# interface.net
KiCad netlist of a schematic drawn in EAGLE
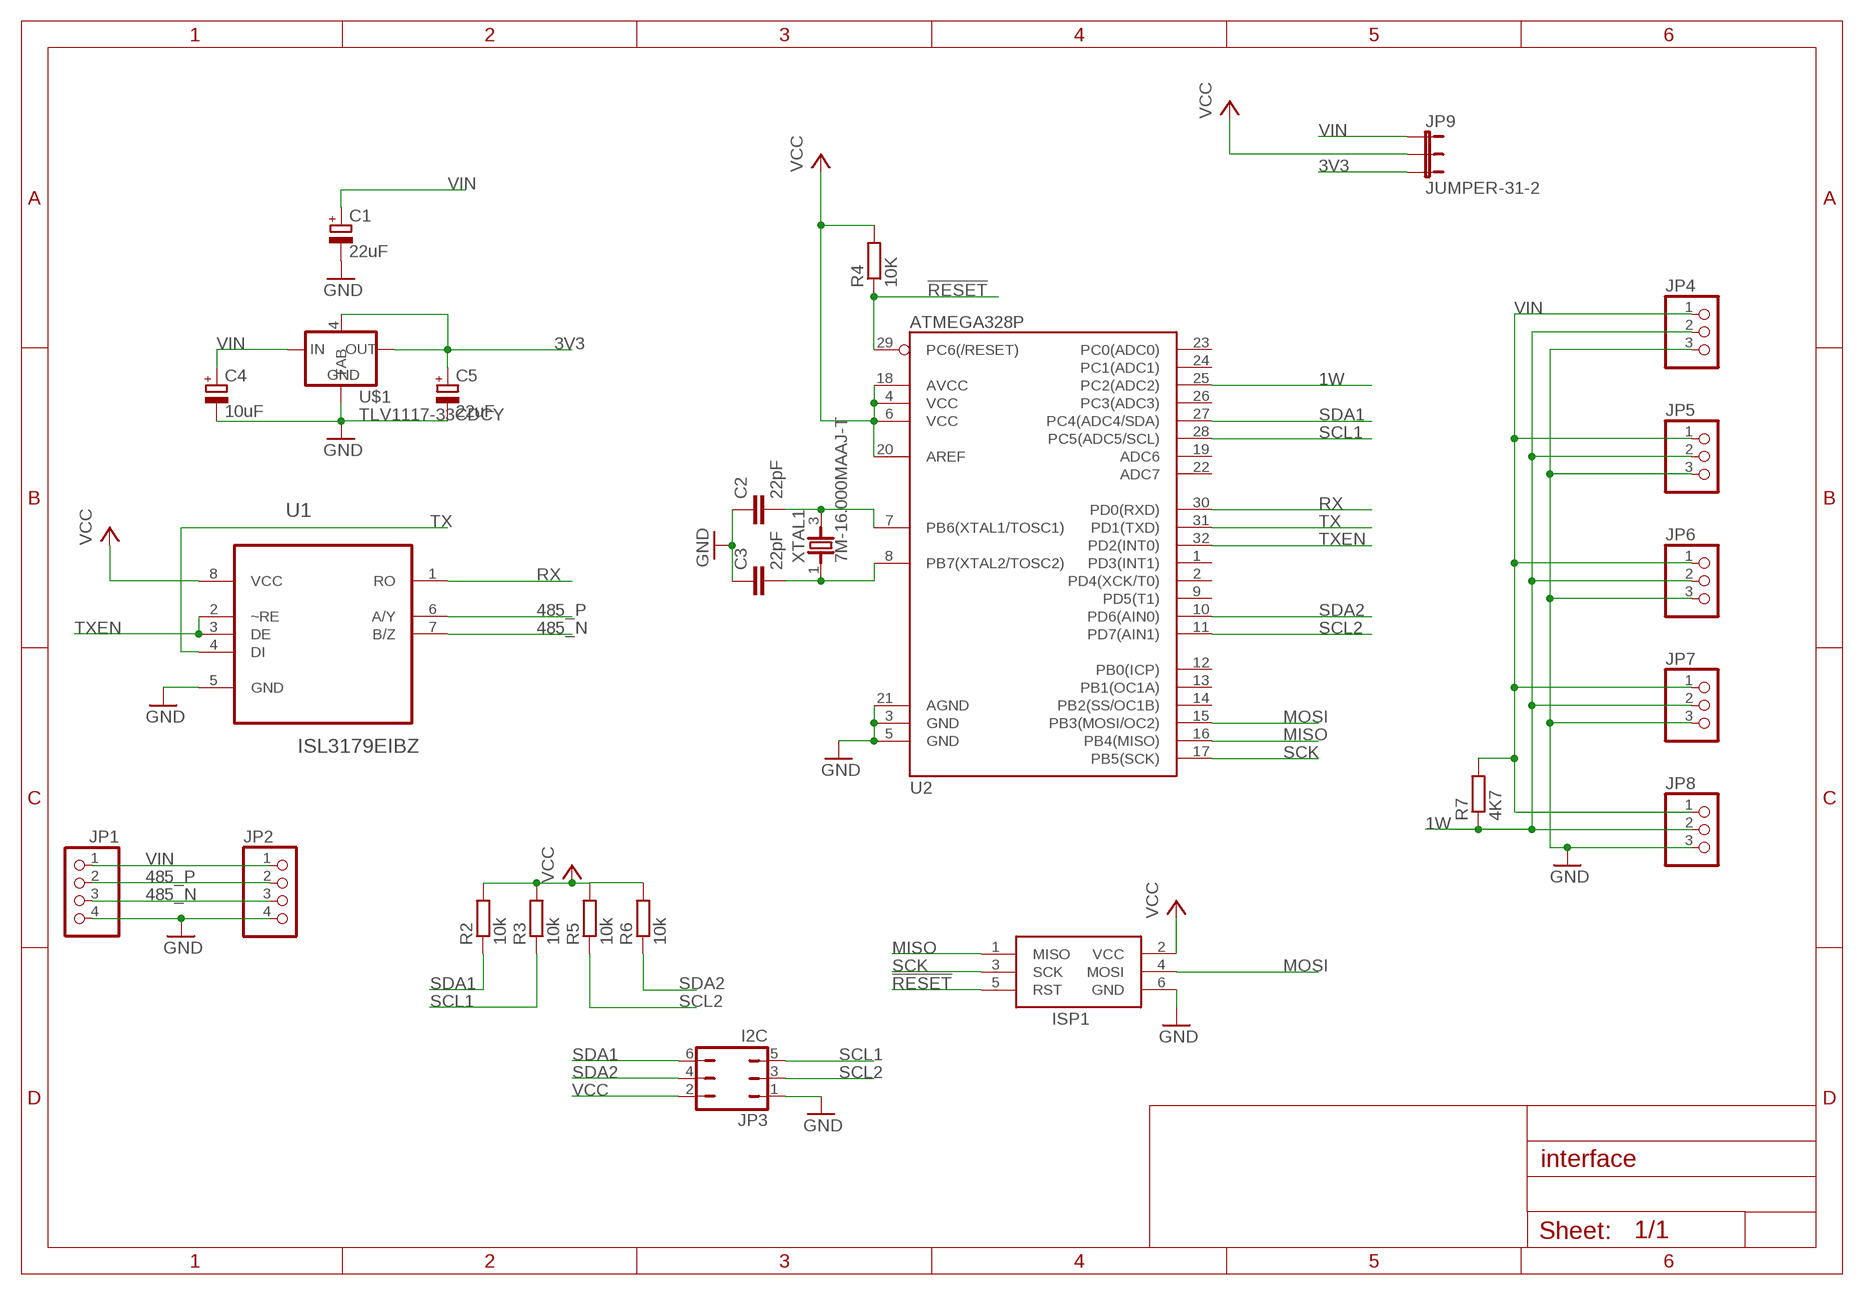
[diagram p0: schematic, sheet 1]

(export (version "E")
  (design (tool "Eeschema 10.0.6"))
  (components
    (comp (ref "C1")
      (value "22uF")
      (footprint "eagle-import:A_3216-18R")
      (libsource (lib "eagle-import") (part "CPOL-EUA/3216-18R"))
    )
    (comp (ref "C2")
      (value "22pF")
      (footprint "eagle-import:C0805")
      (libsource (lib "eagle-import") (part "C-EUC0805"))
    )
    (comp (ref "C3")
      (value "22pF")
      (footprint "eagle-import:C0805")
      (libsource (lib "eagle-import") (part "C-EUC0805"))
    )
    (comp (ref "C4")
      (value "10uF")
      (footprint "eagle-import:A_3216-18R")
      (libsource (lib "eagle-import") (part "CPOL-EUA/3216-18R"))
    )
    (comp (ref "C5")
      (value "22uF")
      (footprint "eagle-import:A_3216-18R")
      (libsource (lib "eagle-import") (part "CPOL-EUA/3216-18R"))
    )
    (comp (ref "ISP1")
      (value "AVRISP-6")
      (footprint "eagle-import:AVRISP")
      (libsource (lib "eagle-import") (part "AVRISP-6"))
    )
    (comp (ref "JP1")
      (value "PINHD-1X4")
      (footprint "eagle-import:1X04")
      (libsource (lib "eagle-import") (part "PINHD-1X4"))
    )
    (comp (ref "JP2")
      (value "PINHD-1X4")
      (footprint "eagle-import:1X04")
      (libsource (lib "eagle-import") (part "PINHD-1X4"))
    )
    (comp (ref "JP3")
      (value "I2C")
      (footprint "eagle-import:JP3Q")
      (libsource (lib "eagle-import") (part "JP3Q"))
    )
    (comp (ref "JP4")
      (value "PINHD-1X3")
      (footprint "eagle-import:1X03")
      (libsource (lib "eagle-import") (part "PINHD-1X3"))
    )
    (comp (ref "JP5")
      (value "PINHD-1X3")
      (footprint "eagle-import:1X03")
      (libsource (lib "eagle-import") (part "PINHD-1X3"))
    )
    (comp (ref "JP6")
      (value "PINHD-1X3")
      (footprint "eagle-import:1X03")
      (libsource (lib "eagle-import") (part "PINHD-1X3"))
    )
    (comp (ref "JP7")
      (value "PINHD-1X3")
      (footprint "eagle-import:1X03")
      (libsource (lib "eagle-import") (part "PINHD-1X3"))
    )
    (comp (ref "JP8")
      (value "PINHD-1X3")
      (footprint "eagle-import:1X03")
      (libsource (lib "eagle-import") (part "PINHD-1X3"))
    )
    (comp (ref "JP9")
      (value "JUMPER-31-2")
      (footprint "eagle-import:SJ_3_PASTE1&2")
      (libsource (lib "eagle-import") (part "JUMPER-31-2"))
    )
    (comp (ref "R2")
      (value "10k")
      (footprint "eagle-import:R0805")
      (libsource (lib "eagle-import") (part "R-EU_R0805"))
    )
    (comp (ref "R3")
      (value "10k")
      (footprint "eagle-import:R0805")
      (libsource (lib "eagle-import") (part "R-EU_R0805"))
    )
    (comp (ref "R4")
      (value "10K")
      (footprint "eagle-import:R0805")
      (libsource (lib "eagle-import") (part "R-EU_R0805"))
    )
    (comp (ref "R5")
      (value "10k")
      (footprint "eagle-import:R0805")
      (libsource (lib "eagle-import") (part "R-EU_R0805"))
    )
    (comp (ref "R6")
      (value "10k")
      (footprint "eagle-import:R0805")
      (libsource (lib "eagle-import") (part "R-EU_R0805"))
    )
    (comp (ref "R7")
      (value "4K7")
      (footprint "eagle-import:R0805")
      (libsource (lib "eagle-import") (part "R-EU_R0805"))
    )
    (comp (ref "U$1")
      (value "TLV1117-33CDCY")
      (footprint "eagle-import:SOT223")
      (libsource (lib "eagle-import") (part "TLV1117-33CDCY"))
    )
    (comp (ref "U1")
      (value "ISL3179EIBZ")
      (footprint "eagle-import:SOIC127P600X175-8N")
      (libsource (lib "eagle-import") (part "ISL3179EIBZ"))
    )
    (comp (ref "U2")
      (value "ATMEGA328P")
      (footprint "eagle-import:TQFP32-08")
      (libsource (lib "eagle-import") (part "ATMEGA328_SMT"))
    )
    (comp (ref "XTAL1")
      (value "7M-16.000MAAJ-T")
      (footprint "eagle-import:TXC_7M-16.000MAAJ-T")
      (fields (field (name "MPN") "7M-16.000MAAJ-T "))
      (libsource (lib "eagle-import") (part "7M-16.000MAAJ-T"))
    )
  )
  (nets
    (net (code "1") (name "/1W") (class "Default")
      (node (ref "JP4") (pin "2") (pinfunction "2_2") (pintype "passive"))
      (node (ref "JP5") (pin "2") (pinfunction "2_2") (pintype "passive"))
      (node (ref "JP6") (pin "2") (pinfunction "2_2") (pintype "passive"))
      (node (ref "JP7") (pin "2") (pinfunction "2_2") (pintype "passive"))
      (node (ref "JP8") (pin "2") (pinfunction "2_2") (pintype "passive"))
      (node (ref "R7") (pin "1") (pinfunction "1_1") (pintype "passive"))
      (node (ref "U2") (pin "25") (pinfunction "PC2(ADC2)_25") (pintype "bidirectional"))
    )
    (net (code "2") (name "/3V3") (class "Default")
      (node (ref "C5") (pin "+") (pinfunction "+_+") (pintype "passive"))
      (node (ref "JP9") (pin "3") (pinfunction "3_3") (pintype "passive"))
      (node (ref "U$1") (pin "2") (pinfunction "OUT_2") (pintype "passive"))
      (node (ref "U$1") (pin "4") (pinfunction "TAB_4") (pintype "passive"))
    )
    (net (code "3") (name "/485_N") (class "Default")
      (node (ref "JP1") (pin "3") (pinfunction "3_3") (pintype "passive"))
      (node (ref "JP2") (pin "3") (pinfunction "3_3") (pintype "passive"))
      (node (ref "U1") (pin "7") (pinfunction "B/Z_7") (pintype "bidirectional"))
    )
    (net (code "4") (name "/485_P") (class "Default")
      (node (ref "JP1") (pin "2") (pinfunction "2_2") (pintype "passive"))
      (node (ref "JP2") (pin "2") (pinfunction "2_2") (pintype "passive"))
      (node (ref "U1") (pin "6") (pinfunction "A/Y_6") (pintype "bidirectional"))
    )
    (net (code "5") (name "/MISO") (class "Default")
      (node (ref "ISP1") (pin "1") (pinfunction "MISO_1") (pintype "input"))
      (node (ref "U2") (pin "16") (pinfunction "PB4(MISO)_16") (pintype "bidirectional"))
    )
    (net (code "6") (name "/MOSI") (class "Default")
      (node (ref "ISP1") (pin "4") (pinfunction "MOSI_4") (pintype "output"))
      (node (ref "U2") (pin "15") (pinfunction "PB3(MOSI/OC2)_15") (pintype "bidirectional"))
    )
    (net (code "7") (name "/RX") (class "Default")
      (node (ref "U1") (pin "1") (pinfunction "RO_1") (pintype "output"))
      (node (ref "U2") (pin "30") (pinfunction "PD0(RXD)_30") (pintype "bidirectional"))
    )
    (net (code "8") (name "/SCK") (class "Default")
      (node (ref "ISP1") (pin "3") (pinfunction "SCK_3") (pintype "output"))
      (node (ref "U2") (pin "17") (pinfunction "PB5(SCK)_17") (pintype "bidirectional"))
    )
    (net (code "9") (name "/SCL1") (class "Default")
      (node (ref "JP3") (pin "5") (pinfunction "5_5") (pintype "passive"))
      (node (ref "R3") (pin "1") (pinfunction "1_1") (pintype "passive"))
      (node (ref "U2") (pin "28") (pinfunction "PC5(ADC5/SCL)_28") (pintype "bidirectional"))
    )
    (net (code "10") (name "/SCL2") (class "Default")
      (node (ref "JP3") (pin "3") (pinfunction "3_3") (pintype "passive"))
      (node (ref "R5") (pin "1") (pinfunction "1_1") (pintype "passive"))
      (node (ref "U2") (pin "11") (pinfunction "PD7(AIN1)_11") (pintype "bidirectional"))
    )
    (net (code "11") (name "/SDA1") (class "Default")
      (node (ref "JP3") (pin "6") (pinfunction "6_6") (pintype "passive"))
      (node (ref "R2") (pin "1") (pinfunction "1_1") (pintype "passive"))
      (node (ref "U2") (pin "27") (pinfunction "PC4(ADC4/SDA)_27") (pintype "bidirectional"))
    )
    (net (code "12") (name "/SDA2") (class "Default")
      (node (ref "JP3") (pin "4") (pinfunction "4_4") (pintype "passive"))
      (node (ref "R6") (pin "1") (pinfunction "1_1") (pintype "passive"))
      (node (ref "U2") (pin "10") (pinfunction "PD6(AIN0)_10") (pintype "bidirectional"))
    )
    (net (code "13") (name "/TX") (class "Default")
      (node (ref "U1") (pin "4") (pinfunction "DI_4") (pintype "input"))
      (node (ref "U2") (pin "31") (pinfunction "PD1(TXD)_31") (pintype "bidirectional"))
    )
    (net (code "14") (name "/TXEN") (class "Default")
      (node (ref "U1") (pin "2") (pinfunction "~{RE}_2") (pintype "input"))
      (node (ref "U1") (pin "3") (pinfunction "DE_3") (pintype "input"))
      (node (ref "U2") (pin "32") (pinfunction "PD2(INT0)_32") (pintype "bidirectional"))
    )
    (net (code "15") (name "/VIN") (class "Default")
      (node (ref "C1") (pin "+") (pinfunction "+_+") (pintype "passive"))
      (node (ref "C4") (pin "+") (pinfunction "+_+") (pintype "passive"))
      (node (ref "JP1") (pin "1") (pinfunction "1_1") (pintype "passive"))
      (node (ref "JP2") (pin "1") (pinfunction "1_1") (pintype "passive"))
      (node (ref "JP4") (pin "1") (pinfunction "1_1") (pintype "passive"))
      (node (ref "JP5") (pin "1") (pinfunction "1_1") (pintype "passive"))
      (node (ref "JP6") (pin "1") (pinfunction "1_1") (pintype "passive"))
      (node (ref "JP7") (pin "1") (pinfunction "1_1") (pintype "passive"))
      (node (ref "JP8") (pin "1") (pinfunction "1_1") (pintype "passive"))
      (node (ref "JP9") (pin "1") (pinfunction "1_1") (pintype "passive"))
      (node (ref "R7") (pin "2") (pinfunction "2_2") (pintype "passive"))
      (node (ref "U$1") (pin "3") (pinfunction "IN_3") (pintype "input"))
    )
    (net (code "16") (name "/~{RESET}") (class "Default")
      (node (ref "ISP1") (pin "5") (pinfunction "RST_5") (pintype "output"))
      (node (ref "R4") (pin "1") (pinfunction "1_1") (pintype "passive"))
      (node (ref "U2") (pin "29") (pinfunction "PC6(/RESET)_29") (pintype "bidirectional"))
    )
    (net (code "17") (name "GND") (class "Default")
      (node (ref "C1") (pin "-") (pinfunction "-_-") (pintype "passive"))
      (node (ref "C2") (pin "1") (pinfunction "1_1") (pintype "passive"))
      (node (ref "C3") (pin "1") (pinfunction "1_1") (pintype "passive"))
      (node (ref "C4") (pin "-") (pinfunction "-_-") (pintype "passive"))
      (node (ref "C5") (pin "-") (pinfunction "-_-") (pintype "passive"))
      (node (ref "ISP1") (pin "6") (pinfunction "GND_6") (pintype "power_in"))
      (node (ref "JP1") (pin "4") (pinfunction "4_4") (pintype "passive"))
      (node (ref "JP2") (pin "4") (pinfunction "4_4") (pintype "passive"))
      (node (ref "JP3") (pin "1") (pinfunction "1_1") (pintype "passive"))
      (node (ref "JP4") (pin "3") (pinfunction "3_3") (pintype "passive"))
      (node (ref "JP5") (pin "3") (pinfunction "3_3") (pintype "passive"))
      (node (ref "JP6") (pin "3") (pinfunction "3_3") (pintype "passive"))
      (node (ref "JP7") (pin "3") (pinfunction "3_3") (pintype "passive"))
      (node (ref "JP8") (pin "3") (pinfunction "3_3") (pintype "passive"))
      (node (ref "U$1") (pin "1") (pinfunction "GND_1") (pintype "input"))
      (node (ref "U1") (pin "5") (pinfunction "GND_5") (pintype "passive"))
      (node (ref "U2") (pin "21") (pinfunction "AGND_21") (pintype "bidirectional"))
      (node (ref "U2") (pin "3") (pinfunction "GND_3") (pintype "bidirectional"))
      (node (ref "U2") (pin "5") (pinfunction "GND_5") (pintype "bidirectional"))
    )
    (net (code "18") (name "Net-(U2-PB6(XTAL1{slash}TOSC1))") (class "Default")
      (node (ref "C2") (pin "2") (pinfunction "2_2") (pintype "passive"))
      (node (ref "U2") (pin "7") (pinfunction "PB6(XTAL1/TOSC1)_7") (pintype "bidirectional"))
      (node (ref "XTAL1") (pin "3") (pinfunction "3_3") (pintype "passive"))
    )
    (net (code "19") (name "Net-(U2-PB7(XTAL2{slash}TOSC2))") (class "Default")
      (node (ref "C3") (pin "2") (pinfunction "2_2") (pintype "passive"))
      (node (ref "U2") (pin "8") (pinfunction "PB7(XTAL2/TOSC2)_8") (pintype "bidirectional"))
      (node (ref "XTAL1") (pin "1") (pinfunction "1_1") (pintype "passive"))
    )
    (net (code "20") (name "VCC") (class "Default")
      (node (ref "ISP1") (pin "2") (pinfunction "VCC_2") (pintype "power_in"))
      (node (ref "JP3") (pin "2") (pinfunction "2_2") (pintype "passive"))
      (node (ref "JP9") (pin "2") (pinfunction "2_2") (pintype "passive"))
      (node (ref "R2") (pin "2") (pinfunction "2_2") (pintype "passive"))
      (node (ref "R3") (pin "2") (pinfunction "2_2") (pintype "passive"))
      (node (ref "R4") (pin "2") (pinfunction "2_2") (pintype "passive"))
      (node (ref "R5") (pin "2") (pinfunction "2_2") (pintype "passive"))
      (node (ref "R6") (pin "2") (pinfunction "2_2") (pintype "passive"))
      (node (ref "U1") (pin "8") (pinfunction "VCC_8") (pintype "power_in"))
      (node (ref "U2") (pin "18") (pinfunction "AVCC_18") (pintype "bidirectional"))
      (node (ref "U2") (pin "20") (pinfunction "AREF_20") (pintype "bidirectional"))
      (node (ref "U2") (pin "4") (pinfunction "VCC_4") (pintype "bidirectional"))
      (node (ref "U2") (pin "6") (pinfunction "VCC_6") (pintype "bidirectional"))
    )
    (net (code "21") (name "unconnected-(U2-ADC6-Pad19)") (class "Default")
      (node (ref "U2") (pin "19") (pinfunction "ADC6_19") (pintype "bidirectional"))
    )
    (net (code "22") (name "unconnected-(U2-ADC7-Pad22)") (class "Default")
      (node (ref "U2") (pin "22") (pinfunction "ADC7_22") (pintype "bidirectional"))
    )
    (net (code "23") (name "unconnected-(U2-PB0(ICP)-Pad12)") (class "Default")
      (node (ref "U2") (pin "12") (pinfunction "PB0(ICP)_12") (pintype "bidirectional"))
    )
    (net (code "24") (name "unconnected-(U2-PB1(OC1A)-Pad13)") (class "Default")
      (node (ref "U2") (pin "13") (pinfunction "PB1(OC1A)_13") (pintype "bidirectional"))
    )
    (net (code "25") (name "unconnected-(U2-PB2(SS{slash}OC1B)-Pad14)") (class "Default")
      (node (ref "U2") (pin "14") (pinfunction "PB2(SS/OC1B)_14") (pintype "bidirectional"))
    )
    (net (code "26") (name "unconnected-(U2-PC0(ADC0)-Pad23)") (class "Default")
      (node (ref "U2") (pin "23") (pinfunction "PC0(ADC0)_23") (pintype "bidirectional"))
    )
    (net (code "27") (name "unconnected-(U2-PC1(ADC1)-Pad24)") (class "Default")
      (node (ref "U2") (pin "24") (pinfunction "PC1(ADC1)_24") (pintype "bidirectional"))
    )
    (net (code "28") (name "unconnected-(U2-PC3(ADC3)-Pad26)") (class "Default")
      (node (ref "U2") (pin "26") (pinfunction "PC3(ADC3)_26") (pintype "bidirectional"))
    )
    (net (code "29") (name "unconnected-(U2-PD3(INT1)-Pad1)") (class "Default")
      (node (ref "U2") (pin "1") (pinfunction "PD3(INT1)_1") (pintype "bidirectional"))
    )
    (net (code "30") (name "unconnected-(U2-PD4(XCK{slash}T0)-Pad2)") (class "Default")
      (node (ref "U2") (pin "2") (pinfunction "PD4(XCK/T0)_2") (pintype "bidirectional"))
    )
    (net (code "31") (name "unconnected-(U2-PD5(T1)-Pad9)") (class "Default")
      (node (ref "U2") (pin "9") (pinfunction "PD5(T1)_9") (pintype "bidirectional"))
    )
  )
)
